# FFC_pcb_v1_double_layer.net
KiCad netlist of a schematic drawn in EAGLE
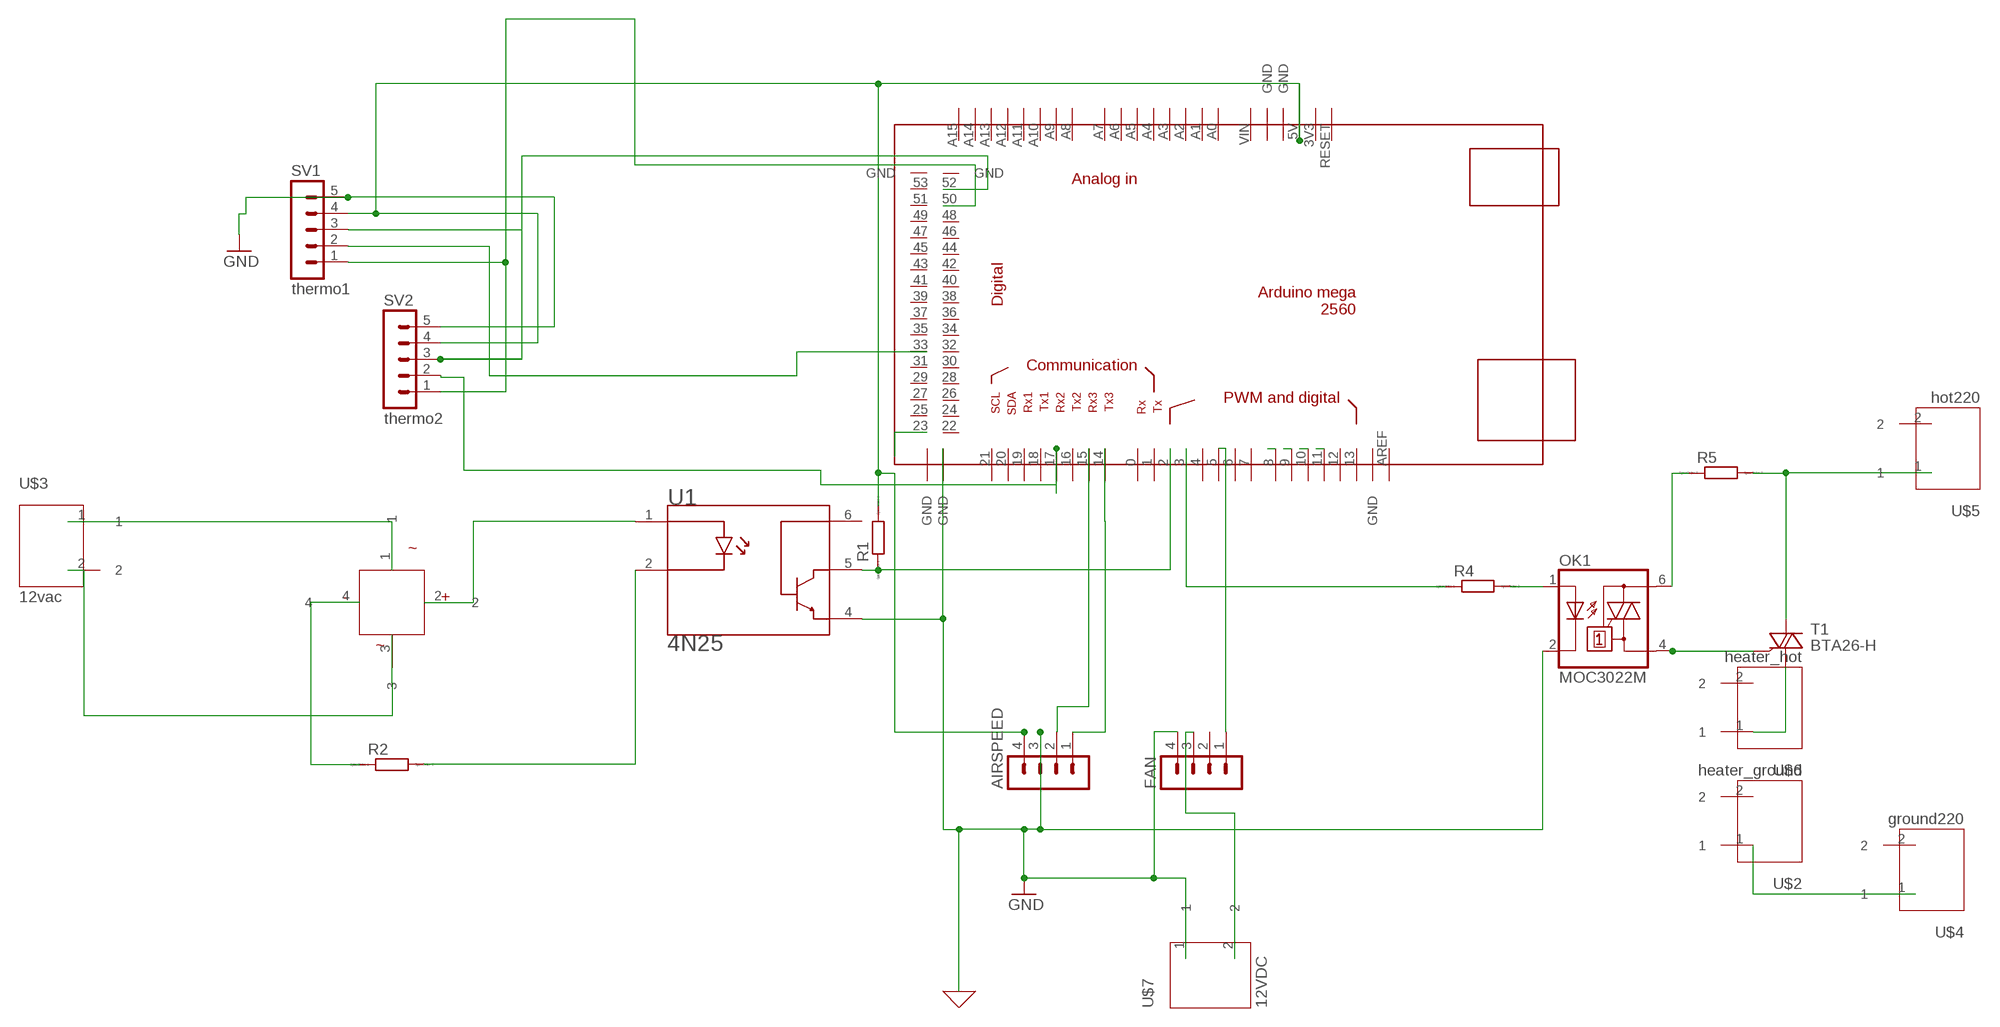
[diagram p0: schematic, sheet 1]

(export (version "E")
  (design (tool "Eeschema 10.0.6"))
  (components
    (comp (ref "AIRSPEED")
      (value "MA04-1")
      (footprint "eagle-import:MA04-1")
      (libsource (lib "eagle-import") (part "MA04-1"))
    )
    (comp (ref "FAN")
      (value "MA04-1")
      (footprint "eagle-import:MA04-1")
      (libsource (lib "eagle-import") (part "MA04-1"))
    )
    (comp (ref "OK1")
      (value "MOC3022M")
      (footprint "eagle-import:DIL06")
      (fields (field (name "MF") "FAIRCHILD SEMICONDUCTOR") (field (name "MPN") "MOC3022-M"))
      (libsource (lib "eagle-import") (part "MOC30M22"))
    )
    (comp (ref "R1")
      (value "R0204/7")
      (footprint "eagle-import:0204_7")
      (libsource (lib "eagle-import") (part "R0204/7"))
    )
    (comp (ref "R2")
      (value "R0204/7")
      (footprint "eagle-import:0204_7")
      (libsource (lib "eagle-import") (part "R0204/7"))
    )
    (comp (ref "R4")
      (value "R0204/7")
      (footprint "eagle-import:0204_7")
      (libsource (lib "eagle-import") (part "R0204/7"))
    )
    (comp (ref "R5")
      (value "R0204/7")
      (footprint "eagle-import:0204_7")
      (libsource (lib "eagle-import") (part "R0204/7"))
    )
    (comp (ref "SV1")
      (value "thermo1")
      (footprint "eagle-import:MA05-1")
      (libsource (lib "eagle-import") (part "MA05-1"))
    )
    (comp (ref "SV2")
      (value "thermo2")
      (footprint "eagle-import:MA05-1")
      (libsource (lib "eagle-import") (part "MA05-1"))
    )
    (comp (ref "T1")
      (value "BTA26-H")
      (footprint "eagle-import:TOP3L-1")
      (libsource (lib "eagle-import") (part "BTA26-H"))
    )
    (comp (ref "U$1")
      (value "MEGA_DEVICE")
      (footprint "eagle-import:MEGABOX")
      (libsource (lib "eagle-import") (part "MEGA_DEVICE"))
    )
    (comp (ref "U$2")
      (value "heater_ground")
      (footprint "eagle-import:COVERED_TERMINAL_2PINS")
      (libsource (lib "eagle-import") (part "COVERED_TERMINAL"))
    )
    (comp (ref "U$3")
      (value "12vac")
      (footprint "eagle-import:COVERED_TERMINAL_2PINS")
      (libsource (lib "eagle-import") (part "COVERED_TERMINAL"))
    )
    (comp (ref "U$4")
      (value "ground220")
      (footprint "eagle-import:COVERED_TERMINAL_2PINS")
      (libsource (lib "eagle-import") (part "COVERED_TERMINAL"))
    )
    (comp (ref "U$5")
      (value "hot220")
      (footprint "eagle-import:COVERED_TERMINAL_2PINS")
      (libsource (lib "eagle-import") (part "COVERED_TERMINAL"))
    )
    (comp (ref "U$6")
      (value "heater_hot")
      (footprint "eagle-import:COVERED_TERMINAL_2PINS")
      (libsource (lib "eagle-import") (part "COVERED_TERMINAL"))
    )
    (comp (ref "U$7")
      (value "12VDC")
      (footprint "eagle-import:COVERED_TERMINAL_2PINS")
      (libsource (lib "eagle-import") (part "COVERED_TERMINAL"))
    )
    (comp (ref "U$8")
      (value "BRIDGE")
      (footprint "eagle-import:BRIDGE")
      (libsource (lib "eagle-import") (part "BRIDGE"))
    )
    (comp (ref "U1")
      (value "4N25")
      (footprint "eagle-import:DIP762W50P254L712H400Q6N")
      (fields (field (name "MF") "Vishay Semiconductor"))
      (libsource (lib "eagle-import") (part "4N25"))
    )
  )
  (nets
    (net (code "1") (name "GND") (class "Default")
      (node (ref "AIRSPEED") (pin "3") (pinfunction "3_3") (pintype "passive"))
      (node (ref "FAN") (pin "4") (pinfunction "4_4") (pintype "passive"))
      (node (ref "OK1") (pin "2") (pinfunction "C_2") (pintype "passive"))
      (node (ref "SV1") (pin "5") (pinfunction "5_5") (pintype "passive"))
      (node (ref "SV2") (pin "5") (pinfunction "5_5") (pintype "passive"))
      (node (ref "U$1") (pin "GND@4") (pinfunction "GND_GND@4") (pintype "bidirectional"))
      (node (ref "U$7") (pin "1") (pinfunction "1_1") (pintype "bidirectional"))
      (node (ref "U1") (pin "4") (pinfunction "E_4") (pintype "passive"))
    )
    (net (code "2") (name "Net-(AIRSPEED-Pad1)") (class "Default")
      (node (ref "AIRSPEED") (pin "1") (pinfunction "1_1") (pintype "passive"))
      (node (ref "U$1") (pin "14") (pinfunction "14_14") (pintype "bidirectional"))
    )
    (net (code "3") (name "Net-(AIRSPEED-Pad2)") (class "Default")
      (node (ref "AIRSPEED") (pin "2") (pinfunction "2_2") (pintype "passive"))
      (node (ref "U$1") (pin "15") (pinfunction "15_15") (pintype "bidirectional"))
    )
    (net (code "4") (name "Net-(AIRSPEED-Pad4)") (class "Default")
      (node (ref "AIRSPEED") (pin "4") (pinfunction "4_4") (pintype "passive"))
      (node (ref "R1") (pin "2") (pinfunction "2_2") (pintype "passive"))
      (node (ref "SV1") (pin "4") (pinfunction "4_4") (pintype "passive"))
      (node (ref "SV2") (pin "4") (pinfunction "4_4") (pintype "passive"))
      (node (ref "U$1") (pin "5V") (pinfunction "5V_5V") (pintype "bidirectional"))
    )
    (net (code "5") (name "Net-(FAN-Pad1)") (class "Default")
      (node (ref "FAN") (pin "1") (pinfunction "1_1") (pintype "passive"))
      (node (ref "U$1") (pin "5") (pinfunction "5_5") (pintype "bidirectional"))
    )
    (net (code "6") (name "Net-(FAN-Pad3)") (class "Default")
      (node (ref "FAN") (pin "3") (pinfunction "3_3") (pintype "passive"))
      (node (ref "U$7") (pin "2") (pinfunction "2_2") (pintype "bidirectional"))
    )
    (net (code "7") (name "Net-(OK1-A)") (class "Default")
      (node (ref "OK1") (pin "1") (pinfunction "A_1") (pintype "passive"))
      (node (ref "R4") (pin "2") (pinfunction "2_2") (pintype "passive"))
    )
    (net (code "8") (name "Net-(OK1-A1)") (class "Default")
      (node (ref "OK1") (pin "4") (pinfunction "A1_4") (pintype "passive"))
      (node (ref "T1") (pin "G") (pinfunction "G_G") (pintype "passive"))
    )
    (net (code "9") (name "Net-(OK1-A2)") (class "Default")
      (node (ref "OK1") (pin "6") (pinfunction "A2_6") (pintype "passive"))
      (node (ref "R5") (pin "1") (pinfunction "1_1") (pintype "passive"))
    )
    (net (code "10") (name "Net-(R2-Pad1)") (class "Default")
      (node (ref "R2") (pin "1") (pinfunction "1_1") (pintype "passive"))
      (node (ref "U$8") (pin "4") (pinfunction "4_4") (pintype "bidirectional"))
    )
    (net (code "11") (name "Net-(R4-Pad1)") (class "Default")
      (node (ref "R4") (pin "1") (pinfunction "1_1") (pintype "passive"))
      (node (ref "U$1") (pin "3") (pinfunction "3_3") (pintype "bidirectional"))
    )
    (net (code "12") (name "Net-(R5-Pad2)") (class "Default")
      (node (ref "R5") (pin "2") (pinfunction "2_2") (pintype "passive"))
      (node (ref "T1") (pin "A2") (pinfunction "A2_A2") (pintype "passive"))
      (node (ref "U$5") (pin "1") (pinfunction "1_1") (pintype "bidirectional"))
    )
    (net (code "13") (name "Net-(SV1-Pad1)") (class "Default")
      (node (ref "SV1") (pin "1") (pinfunction "1_1") (pintype "passive"))
      (node (ref "SV2") (pin "1") (pinfunction "1_1") (pintype "passive"))
      (node (ref "U$1") (pin "50") (pinfunction "50_50") (pintype "bidirectional"))
    )
    (net (code "14") (name "Net-(SV1-Pad2)") (class "Default")
      (node (ref "SV1") (pin "2") (pinfunction "2_2") (pintype "passive"))
      (node (ref "U$1") (pin "33") (pinfunction "33_33") (pintype "bidirectional"))
    )
    (net (code "15") (name "Net-(SV1-Pad3)") (class "Default")
      (node (ref "SV1") (pin "3") (pinfunction "3_3") (pintype "passive"))
      (node (ref "SV2") (pin "3") (pinfunction "3_3") (pintype "passive"))
      (node (ref "U$1") (pin "52") (pinfunction "52_52") (pintype "bidirectional"))
    )
    (net (code "16") (name "Net-(SV2-Pad2)") (class "Default")
      (node (ref "SV2") (pin "2") (pinfunction "2_2") (pintype "passive"))
      (node (ref "U$1") (pin "17") (pinfunction "17_17") (pintype "bidirectional"))
    )
    (net (code "17") (name "Net-(T1-PadA1)") (class "Default")
      (node (ref "T1") (pin "A1") (pinfunction "A1_A1") (pintype "passive"))
      (node (ref "U$6") (pin "1") (pinfunction "1_1") (pintype "bidirectional"))
    )
    (net (code "18") (name "Net-(U$2-Pad1)") (class "Default")
      (node (ref "U$2") (pin "1") (pinfunction "1_1") (pintype "bidirectional"))
      (node (ref "U$4") (pin "1") (pinfunction "1_1") (pintype "bidirectional"))
    )
    (net (code "19") (name "Net-(U$3-Pad1)") (class "Default")
      (node (ref "U$3") (pin "1") (pinfunction "1_1") (pintype "bidirectional"))
      (node (ref "U$8") (pin "1") (pinfunction "1_1") (pintype "bidirectional"))
    )
    (net (code "20") (name "Net-(U$3-Pad2)") (class "Default")
      (node (ref "U$3") (pin "2") (pinfunction "2_2") (pintype "bidirectional"))
      (node (ref "U$8") (pin "3") (pinfunction "3_3") (pintype "bidirectional"))
    )
    (net (code "21") (name "Net-(U1-A)") (class "Default")
      (node (ref "U$8") (pin "2") (pinfunction "2_2") (pintype "bidirectional"))
      (node (ref "U1") (pin "1") (pinfunction "A_1") (pintype "passive"))
    )
    (net (code "22") (name "Net-(U1-C)") (class "Default")
      (node (ref "R1") (pin "1") (pinfunction "1_1") (pintype "passive"))
      (node (ref "U$1") (pin "2") (pinfunction "2_2") (pintype "bidirectional"))
      (node (ref "U1") (pin "5") (pinfunction "C_5") (pintype "passive"))
    )
    (net (code "23") (name "Net-(U1-K)") (class "Default")
      (node (ref "R2") (pin "2") (pinfunction "2_2") (pintype "passive"))
      (node (ref "U1") (pin "2") (pinfunction "K_2") (pintype "passive"))
    )
    (net (code "24") (name "unconnected-(FAN-Pad2)") (class "Default")
      (node (ref "FAN") (pin "2") (pinfunction "2_2") (pintype "passive"))
    )
    (net (code "25") (name "unconnected-(U$1-GND-PadGND@1)") (class "Default")
      (node (ref "U$1") (pin "GND@1") (pinfunction "GND_GND@1") (pintype "bidirectional"))
    )
    (net (code "26") (name "unconnected-(U$1-GND-PadGND@2)") (class "Default")
      (node (ref "U$1") (pin "GND@2") (pinfunction "GND_GND@2") (pintype "bidirectional"))
    )
    (net (code "27") (name "unconnected-(U$1-GND-PadGND@3)") (class "Default")
      (node (ref "U$1") (pin "GND@3") (pinfunction "GND_GND@3") (pintype "bidirectional"))
    )
    (net (code "28") (name "unconnected-(U$1-GND-PadGND@5)") (class "Default")
      (node (ref "U$1") (pin "GND@5") (pinfunction "GND_GND@5") (pintype "bidirectional"))
    )
    (net (code "29") (name "unconnected-(U$1-GND-PadGND@6)") (class "Default")
      (node (ref "U$1") (pin "GND@6") (pinfunction "GND_GND@6") (pintype "bidirectional"))
    )
    (net (code "30") (name "unconnected-(U$1-GND-PadGND@7)") (class "Default")
      (node (ref "U$1") (pin "GND@7") (pinfunction "GND_GND@7") (pintype "bidirectional"))
    )
    (net (code "31") (name "unconnected-(U$1-Pad0)") (class "Default")
      (node (ref "U$1") (pin "0") (pinfunction "0_0") (pintype "bidirectional"))
    )
    (net (code "32") (name "unconnected-(U$1-Pad1)") (class "Default")
      (node (ref "U$1") (pin "1") (pinfunction "1_1") (pintype "bidirectional"))
    )
    (net (code "33") (name "unconnected-(U$1-Pad3V3)") (class "Default")
      (node (ref "U$1") (pin "3V3") (pinfunction "3V3_3V3") (pintype "bidirectional"))
    )
    (net (code "34") (name "unconnected-(U$1-Pad4)") (class "Default")
      (node (ref "U$1") (pin "4") (pinfunction "4_4") (pintype "bidirectional"))
    )
    (net (code "35") (name "unconnected-(U$1-Pad6)") (class "Default")
      (node (ref "U$1") (pin "6") (pinfunction "6_6") (pintype "bidirectional"))
    )
    (net (code "36") (name "unconnected-(U$1-Pad7)") (class "Default")
      (node (ref "U$1") (pin "7") (pinfunction "7_7") (pintype "bidirectional"))
    )
    (net (code "37") (name "unconnected-(U$1-Pad8)") (class "Default")
      (node (ref "U$1") (pin "8") (pinfunction "8_8") (pintype "bidirectional"))
    )
    (net (code "38") (name "unconnected-(U$1-Pad9)") (class "Default")
      (node (ref "U$1") (pin "9") (pinfunction "9_9") (pintype "bidirectional"))
    )
    (net (code "39") (name "unconnected-(U$1-Pad10)") (class "Default")
      (node (ref "U$1") (pin "10") (pinfunction "10_10") (pintype "bidirectional"))
    )
    (net (code "40") (name "unconnected-(U$1-Pad11)") (class "Default")
      (node (ref "U$1") (pin "11") (pinfunction "11_11") (pintype "bidirectional"))
    )
    (net (code "41") (name "unconnected-(U$1-Pad12)") (class "Default")
      (node (ref "U$1") (pin "12") (pinfunction "12_12") (pintype "bidirectional"))
    )
    (net (code "42") (name "unconnected-(U$1-Pad13)") (class "Default")
      (node (ref "U$1") (pin "13") (pinfunction "13_13") (pintype "bidirectional"))
    )
    (net (code "43") (name "unconnected-(U$1-Pad16)") (class "Default")
      (node (ref "U$1") (pin "16") (pinfunction "16_16") (pintype "bidirectional"))
    )
    (net (code "44") (name "unconnected-(U$1-Pad18)") (class "Default")
      (node (ref "U$1") (pin "18") (pinfunction "18_18") (pintype "bidirectional"))
    )
    (net (code "45") (name "unconnected-(U$1-Pad19)") (class "Default")
      (node (ref "U$1") (pin "19") (pinfunction "19_19") (pintype "bidirectional"))
    )
    (net (code "46") (name "unconnected-(U$1-Pad20)") (class "Default")
      (node (ref "U$1") (pin "20") (pinfunction "20_20") (pintype "bidirectional"))
    )
    (net (code "47") (name "unconnected-(U$1-Pad21)") (class "Default")
      (node (ref "U$1") (pin "21") (pinfunction "21_21") (pintype "bidirectional"))
    )
    (net (code "48") (name "unconnected-(U$1-Pad22)") (class "Default")
      (node (ref "U$1") (pin "22") (pinfunction "22_22") (pintype "bidirectional"))
    )
    (net (code "49") (name "unconnected-(U$1-Pad23)") (class "Default")
      (node (ref "U$1") (pin "23") (pinfunction "23_23") (pintype "bidirectional"))
    )
    (net (code "50") (name "unconnected-(U$1-Pad24)") (class "Default")
      (node (ref "U$1") (pin "24") (pinfunction "24_24") (pintype "bidirectional"))
    )
    (net (code "51") (name "unconnected-(U$1-Pad25)") (class "Default")
      (node (ref "U$1") (pin "25") (pinfunction "25_25") (pintype "bidirectional"))
    )
    (net (code "52") (name "unconnected-(U$1-Pad26)") (class "Default")
      (node (ref "U$1") (pin "26") (pinfunction "26_26") (pintype "bidirectional"))
    )
    (net (code "53") (name "unconnected-(U$1-Pad27)") (class "Default")
      (node (ref "U$1") (pin "27") (pinfunction "27_27") (pintype "bidirectional"))
    )
    (net (code "54") (name "unconnected-(U$1-Pad28)") (class "Default")
      (node (ref "U$1") (pin "28") (pinfunction "28_28") (pintype "bidirectional"))
    )
    (net (code "55") (name "unconnected-(U$1-Pad29)") (class "Default")
      (node (ref "U$1") (pin "29") (pinfunction "29_29") (pintype "bidirectional"))
    )
    (net (code "56") (name "unconnected-(U$1-Pad30)") (class "Default")
      (node (ref "U$1") (pin "30") (pinfunction "30_30") (pintype "bidirectional"))
    )
    (net (code "57") (name "unconnected-(U$1-Pad31)") (class "Default")
      (node (ref "U$1") (pin "31") (pinfunction "31_31") (pintype "bidirectional"))
    )
    (net (code "58") (name "unconnected-(U$1-Pad32)") (class "Default")
      (node (ref "U$1") (pin "32") (pinfunction "32_32") (pintype "bidirectional"))
    )
    (net (code "59") (name "unconnected-(U$1-Pad34)") (class "Default")
      (node (ref "U$1") (pin "34") (pinfunction "34_34") (pintype "bidirectional"))
    )
    (net (code "60") (name "unconnected-(U$1-Pad35)") (class "Default")
      (node (ref "U$1") (pin "35") (pinfunction "35_35") (pintype "bidirectional"))
    )
    (net (code "61") (name "unconnected-(U$1-Pad36)") (class "Default")
      (node (ref "U$1") (pin "36") (pinfunction "36_36") (pintype "bidirectional"))
    )
    (net (code "62") (name "unconnected-(U$1-Pad37)") (class "Default")
      (node (ref "U$1") (pin "37") (pinfunction "37_37") (pintype "bidirectional"))
    )
    (net (code "63") (name "unconnected-(U$1-Pad38)") (class "Default")
      (node (ref "U$1") (pin "38") (pinfunction "38_38") (pintype "bidirectional"))
    )
    (net (code "64") (name "unconnected-(U$1-Pad39)") (class "Default")
      (node (ref "U$1") (pin "39") (pinfunction "39_39") (pintype "bidirectional"))
    )
    (net (code "65") (name "unconnected-(U$1-Pad40)") (class "Default")
      (node (ref "U$1") (pin "40") (pinfunction "40_40") (pintype "bidirectional"))
    )
    (net (code "66") (name "unconnected-(U$1-Pad41)") (class "Default")
      (node (ref "U$1") (pin "41") (pinfunction "41_41") (pintype "bidirectional"))
    )
    (net (code "67") (name "unconnected-(U$1-Pad42)") (class "Default")
      (node (ref "U$1") (pin "42") (pinfunction "42_42") (pintype "bidirectional"))
    )
    (net (code "68") (name "unconnected-(U$1-Pad43)") (class "Default")
      (node (ref "U$1") (pin "43") (pinfunction "43_43") (pintype "bidirectional"))
    )
    (net (code "69") (name "unconnected-(U$1-Pad44)") (class "Default")
      (node (ref "U$1") (pin "44") (pinfunction "44_44") (pintype "bidirectional"))
    )
    (net (code "70") (name "unconnected-(U$1-Pad45)") (class "Default")
      (node (ref "U$1") (pin "45") (pinfunction "45_45") (pintype "bidirectional"))
    )
    (net (code "71") (name "unconnected-(U$1-Pad46)") (class "Default")
      (node (ref "U$1") (pin "46") (pinfunction "46_46") (pintype "bidirectional"))
    )
    (net (code "72") (name "unconnected-(U$1-Pad47)") (class "Default")
      (node (ref "U$1") (pin "47") (pinfunction "47_47") (pintype "bidirectional"))
    )
    (net (code "73") (name "unconnected-(U$1-Pad48)") (class "Default")
      (node (ref "U$1") (pin "48") (pinfunction "48_48") (pintype "bidirectional"))
    )
    (net (code "74") (name "unconnected-(U$1-Pad49)") (class "Default")
      (node (ref "U$1") (pin "49") (pinfunction "49_49") (pintype "bidirectional"))
    )
    (net (code "75") (name "unconnected-(U$1-Pad51)") (class "Default")
      (node (ref "U$1") (pin "51") (pinfunction "51_51") (pintype "bidirectional"))
    )
    (net (code "76") (name "unconnected-(U$1-Pad53)") (class "Default")
      (node (ref "U$1") (pin "53") (pinfunction "53_53") (pintype "bidirectional"))
    )
    (net (code "77") (name "unconnected-(U$1-PadA0)") (class "Default")
      (node (ref "U$1") (pin "A0") (pinfunction "A0_A0") (pintype "bidirectional"))
    )
    (net (code "78") (name "unconnected-(U$1-PadA1)") (class "Default")
      (node (ref "U$1") (pin "A1") (pinfunction "A1_A1") (pintype "bidirectional"))
    )
    (net (code "79") (name "unconnected-(U$1-PadA2)") (class "Default")
      (node (ref "U$1") (pin "A2") (pinfunction "A2_A2") (pintype "bidirectional"))
    )
    (net (code "80") (name "unconnected-(U$1-PadA3)") (class "Default")
      (node (ref "U$1") (pin "A3") (pinfunction "A3_A3") (pintype "bidirectional"))
    )
    (net (code "81") (name "unconnected-(U$1-PadA4)") (class "Default")
      (node (ref "U$1") (pin "A4") (pinfunction "A4_A4") (pintype "bidirectional"))
    )
    (net (code "82") (name "unconnected-(U$1-PadA5)") (class "Default")
      (node (ref "U$1") (pin "A5") (pinfunction "A5_A5") (pintype "bidirectional"))
    )
    (net (code "83") (name "unconnected-(U$1-PadA6)") (class "Default")
      (node (ref "U$1") (pin "A6") (pinfunction "A6_A6") (pintype "bidirectional"))
    )
    (net (code "84") (name "unconnected-(U$1-PadA7)") (class "Default")
      (node (ref "U$1") (pin "A7") (pinfunction "A7_A7") (pintype "bidirectional"))
    )
    (net (code "85") (name "unconnected-(U$1-PadA8)") (class "Default")
      (node (ref "U$1") (pin "A8") (pinfunction "A8_A8") (pintype "bidirectional"))
    )
    (net (code "86") (name "unconnected-(U$1-PadA9)") (class "Default")
      (node (ref "U$1") (pin "A9") (pinfunction "A9_A9") (pintype "bidirectional"))
    )
    (net (code "87") (name "unconnected-(U$1-PadA10)") (class "Default")
      (node (ref "U$1") (pin "A10") (pinfunction "A10_A10") (pintype "bidirectional"))
    )
    (net (code "88") (name "unconnected-(U$1-PadA11)") (class "Default")
      (node (ref "U$1") (pin "A11") (pinfunction "A11_A11") (pintype "bidirectional"))
    )
    (net (code "89") (name "unconnected-(U$1-PadA12)") (class "Default")
      (node (ref "U$1") (pin "A12") (pinfunction "A12_A12") (pintype "bidirectional"))
    )
    (net (code "90") (name "unconnected-(U$1-PadA13)") (class "Default")
      (node (ref "U$1") (pin "A13") (pinfunction "A13_A13") (pintype "bidirectional"))
    )
    (net (code "91") (name "unconnected-(U$1-PadA14)") (class "Default")
      (node (ref "U$1") (pin "A14") (pinfunction "A14_A14") (pintype "bidirectional"))
    )
    (net (code "92") (name "unconnected-(U$1-PadA15)") (class "Default")
      (node (ref "U$1") (pin "A15") (pinfunction "A15_A15") (pintype "bidirectional"))
    )
    (net (code "93") (name "unconnected-(U$1-PadAREF)") (class "Default")
      (node (ref "U$1") (pin "AREF") (pinfunction "AREF_AREF") (pintype "bidirectional"))
    )
    (net (code "94") (name "unconnected-(U$1-PadRESET)") (class "Default")
      (node (ref "U$1") (pin "RESET") (pinfunction "RESET_RESET") (pintype "bidirectional"))
    )
    (net (code "95") (name "unconnected-(U$1-PadVIN)") (class "Default")
      (node (ref "U$1") (pin "VIN") (pinfunction "VIN_VIN") (pintype "bidirectional"))
    )
    (net (code "96") (name "unconnected-(U$2-Pad2)") (class "Default")
      (node (ref "U$2") (pin "2") (pinfunction "2_2") (pintype "bidirectional"))
    )
    (net (code "97") (name "unconnected-(U$4-Pad2)") (class "Default")
      (node (ref "U$4") (pin "2") (pinfunction "2_2") (pintype "bidirectional"))
    )
    (net (code "98") (name "unconnected-(U$5-Pad2)") (class "Default")
      (node (ref "U$5") (pin "2") (pinfunction "2_2") (pintype "bidirectional"))
    )
    (net (code "99") (name "unconnected-(U$6-Pad2)") (class "Default")
      (node (ref "U$6") (pin "2") (pinfunction "2_2") (pintype "bidirectional"))
    )
    (net (code "100") (name "unconnected-(U1-B-Pad6)") (class "Default")
      (node (ref "U1") (pin "6") (pinfunction "B_6") (pintype "passive"))
    )
  )
)
